# tt-motor_driver_and_encoder.net
KiCad netlist of a schematic drawn in EAGLE
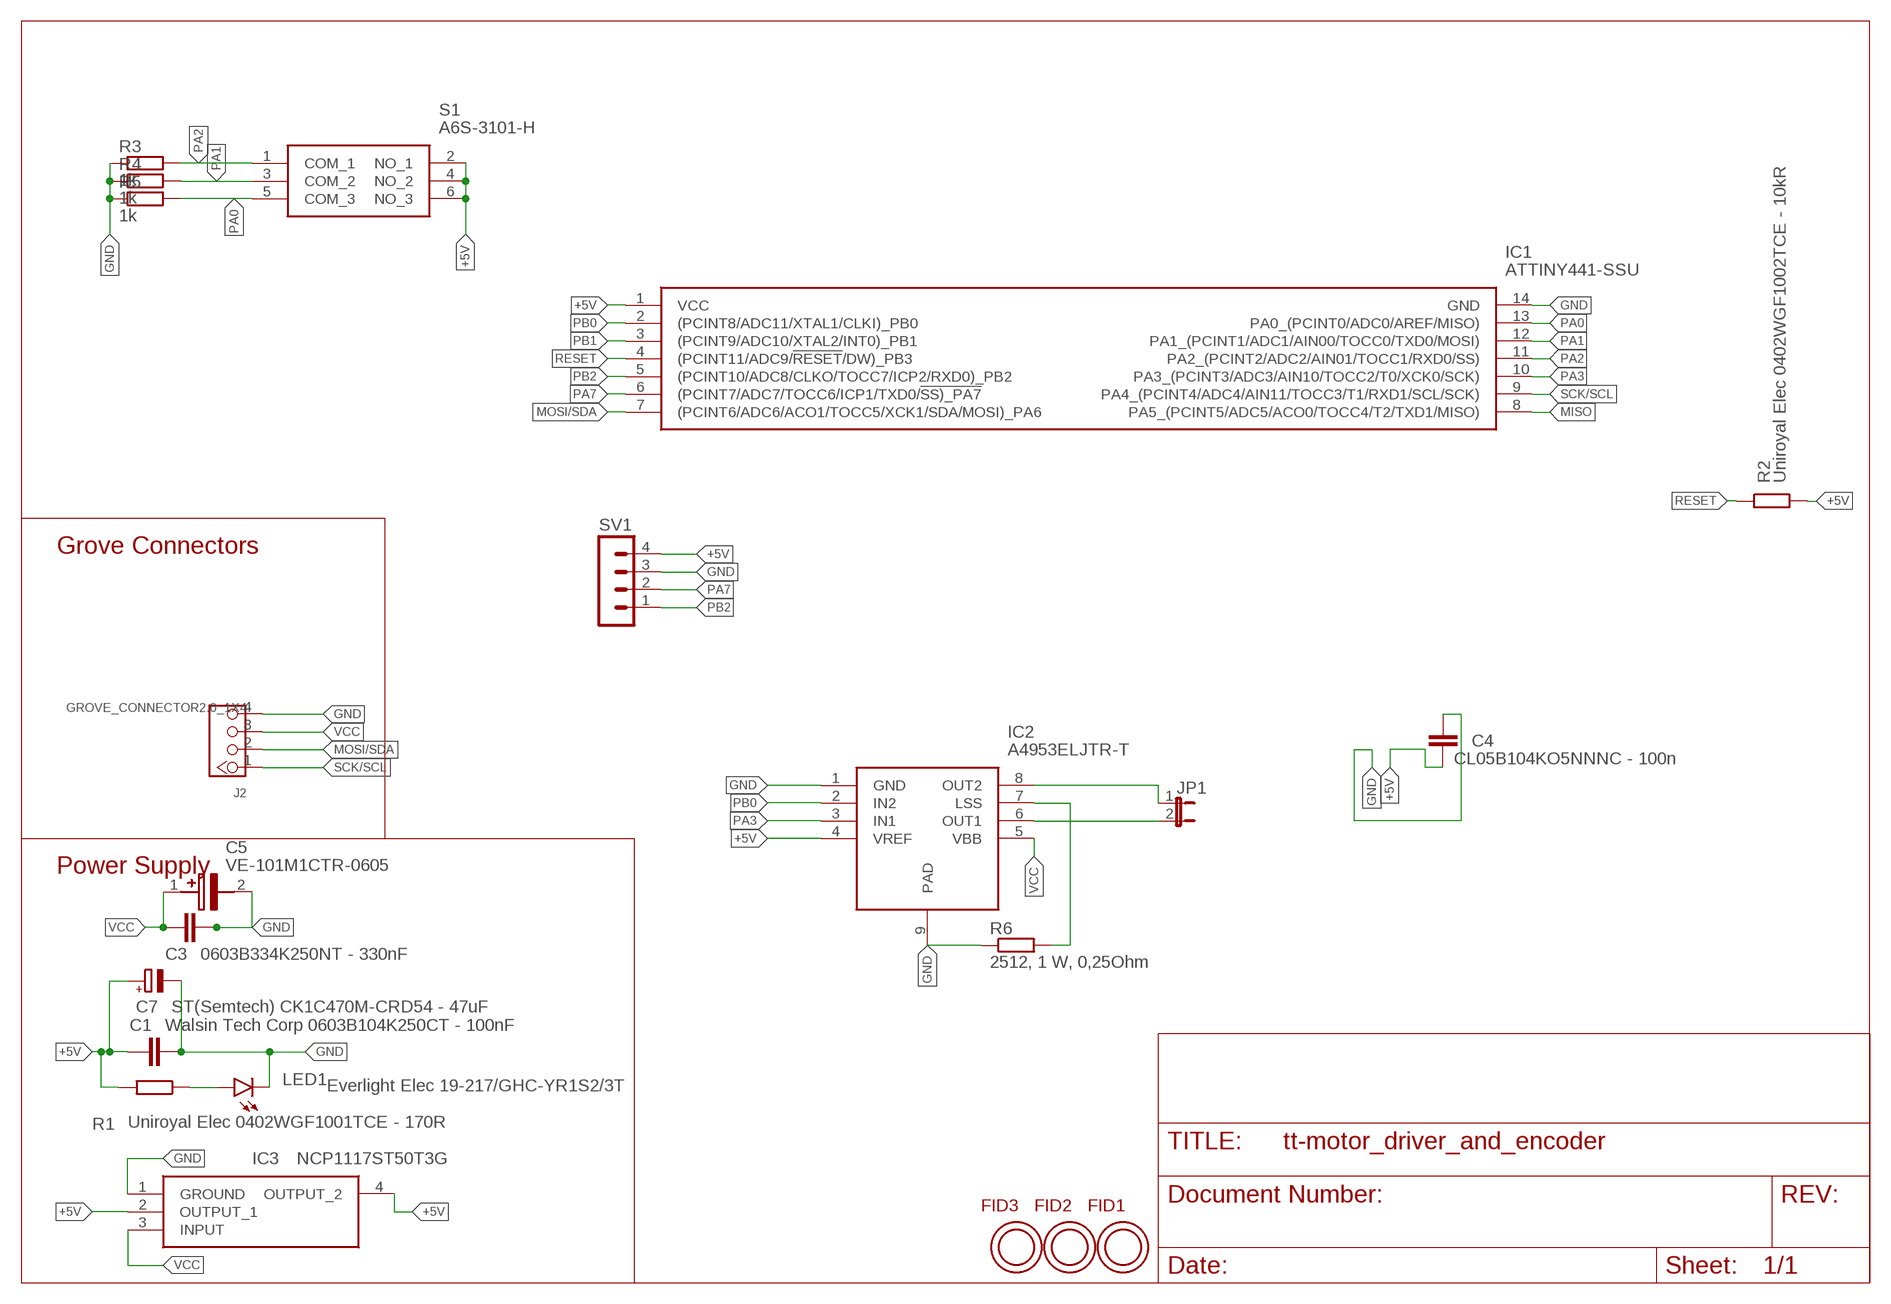
[diagram p0: schematic, sheet 1]

(export (version "E")
  (design (tool "Eeschema 10.0.6"))
  (components
    (comp (ref "C1")
      (value "Walsin Tech Corp 0603B104K250CT - 100nF")
      (footprint "eagle-import:C0603")
      (libsource (lib "eagle-import") (part "C-EUC0603"))
    )
    (comp (ref "C3")
      (value "0603B334K250NT - 330nF")
      (footprint "eagle-import:C0603")
      (libsource (lib "eagle-import") (part "C-EUC0603"))
    )
    (comp (ref "C4")
      (value "CL05B104KO5NNNC - 100n")
      (footprint "eagle-import:C0402")
      (libsource (lib "eagle-import") (part "C-EUC0402"))
    )
    (comp (ref "C5")
      (value "VE-101M1CTR-0605")
      (footprint "eagle-import:CAPAE660X550N")
      (fields (field (name "MOUSER_PART_NUMBER") "140-VE101M1CTR0605"))
      (libsource (lib "eagle-import") (part "VE-101M1CTR-0605"))
    )
    (comp (ref "C7")
      (value "ST(Semtech) CK1C470M-CRD54 - 47uF")
      (footprint "eagle-import:PANASONIC_C")
      (libsource (lib "eagle-import") (part "CPOL-EUC"))
    )
    (comp (ref "FID1")
      (value "OPEN-PNP-FIDUCIAL")
      (footprint "eagle-import:OPEN-PNP-FIDUCIAL")
      (libsource (lib "eagle-import") (part "OPEN-PNP-FIDUCIAL"))
    )
    (comp (ref "FID2")
      (value "OPEN-PNP-FIDUCIAL")
      (footprint "eagle-import:OPEN-PNP-FIDUCIAL")
      (libsource (lib "eagle-import") (part "OPEN-PNP-FIDUCIAL"))
    )
    (comp (ref "FID3")
      (value "OPEN-PNP-FIDUCIAL")
      (footprint "eagle-import:OPEN-PNP-FIDUCIAL")
      (libsource (lib "eagle-import") (part "OPEN-PNP-FIDUCIAL"))
    )
    (comp (ref "IC1")
      (value "ATTINY441-SSU")
      (footprint "eagle-import:SOIC127P600X175-14N")
      (fields (field (name "MOUSER_PART_NUMBER") "556-ATTINY441-SSU"))
      (libsource (lib "eagle-import") (part "ATTINY441-SSU"))
    )
    (comp (ref "IC2")
      (value "A4953ELJTR-T")
      (footprint "eagle-import:SOIC127P600X170-9N")
      (libsource (lib "eagle-import") (part "A4953ELJTR-T"))
    )
    (comp (ref "IC3")
      (value "NCP1117ST50T3G")
      (footprint "eagle-import:SOT230P700X180-4N")
      (fields (field (name "MOUSER_PART_NUMBER") "863-NCP1117ST50T3G"))
      (libsource (lib "eagle-import") (part "NCP1117ST50T3G"))
    )
    (comp (ref "J2")
      (value "GROVE_CONNECTOR2.0_1X4")
      (footprint "eagle-import:2.0_1X4_STRAIGHT")
      (libsource (lib "eagle-import") (part "GROVE_CONNECTOR2.0_1X4"))
    )
    (comp (ref "JP1")
      (value "JP1E")
      (footprint "eagle-import:JP1")
      (libsource (lib "eagle-import") (part "JP1E"))
    )
    (comp (ref "LED1")
      (value "Everlight Elec 19-217/GHC-YR1S2/3T")
      (footprint "eagle-import:CHIPLED_0603")
      (libsource (lib "eagle-import") (part "LEDCHIPLED_0603"))
    )
    (comp (ref "R1")
      (value "Uniroyal Elec 0402WGF1001TCE - 170R")
      (footprint "eagle-import:R0402")
      (libsource (lib "eagle-import") (part "R-EU_R0402"))
    )
    (comp (ref "R2")
      (value "Uniroyal Elec 0402WGF1002TCE - 10kR")
      (footprint "eagle-import:R0402")
      (libsource (lib "eagle-import") (part "R-EU_R0402"))
    )
    (comp (ref "R3")
      (value "1k")
      (footprint "eagle-import:R0402")
      (libsource (lib "eagle-import") (part "R-EU_R0402"))
    )
    (comp (ref "R4")
      (value "1k")
      (footprint "eagle-import:R0402")
      (libsource (lib "eagle-import") (part "R-EU_R0402"))
    )
    (comp (ref "R5")
      (value "1k")
      (footprint "eagle-import:R0402")
      (libsource (lib "eagle-import") (part "R-EU_R0402"))
    )
    (comp (ref "R6")
      (value "2512, 1 W, 0,25Ohm")
      (footprint "eagle-import:R2512")
      (libsource (lib "eagle-import") (part "R-EU_R2512"))
    )
    (comp (ref "S1")
      (value "A6S-3101-H")
      (footprint "eagle-import:A6S3104H")
      (fields (field (name "MOUSER_PART_NUMBER") "653-A6S-3101-H"))
      (libsource (lib "eagle-import") (part "A6S-3101-H"))
    )
    (comp (ref "SV1")
      (value "MA04-1")
      (footprint "eagle-import:MA04-1")
      (libsource (lib "eagle-import") (part "MA04-1"))
    )
  )
  (nets
    (net (code "1") (name "+5V") (class "Default")
      (node (ref "C1") (pin "1") (pinfunction "1_1") (pintype "passive"))
      (node (ref "C4") (pin "1") (pinfunction "1_1") (pintype "passive"))
      (node (ref "C7") (pin "+") (pinfunction "+_+") (pintype "passive"))
      (node (ref "IC1") (pin "1") (pinfunction "VCC_1") (pintype "bidirectional"))
      (node (ref "IC2") (pin "4") (pinfunction "VREF_4") (pintype "input"))
      (node (ref "IC3") (pin "2") (pinfunction "OUTPUT_1_2") (pintype "bidirectional"))
      (node (ref "IC3") (pin "4") (pinfunction "OUTPUT_2_4") (pintype "bidirectional"))
      (node (ref "R1") (pin "2") (pinfunction "2_2") (pintype "passive"))
      (node (ref "R2") (pin "2") (pinfunction "2_2") (pintype "passive"))
      (node (ref "S1") (pin "2") (pinfunction "NO_1_2") (pintype "bidirectional"))
      (node (ref "S1") (pin "4") (pinfunction "NO_2_4") (pintype "bidirectional"))
      (node (ref "S1") (pin "6") (pinfunction "NO_3_6") (pintype "bidirectional"))
      (node (ref "SV1") (pin "4") (pinfunction "4_4") (pintype "passive"))
    )
    (net (code "2") (name "GND") (class "Default")
      (node (ref "C1") (pin "2") (pinfunction "2_2") (pintype "passive"))
      (node (ref "C3") (pin "1") (pinfunction "1_1") (pintype "passive"))
      (node (ref "C4") (pin "2") (pinfunction "2_2") (pintype "passive"))
      (node (ref "C5") (pin "2") (pinfunction "-_2") (pintype "bidirectional"))
      (node (ref "C7") (pin "-") (pinfunction "-_-") (pintype "passive"))
      (node (ref "IC1") (pin "14") (pinfunction "GND_14") (pintype "bidirectional"))
      (node (ref "IC2") (pin "1") (pinfunction "GND_1") (pintype "power_in"))
      (node (ref "IC2") (pin "9") (pinfunction "PAD_9") (pintype "bidirectional"))
      (node (ref "IC3") (pin "1") (pinfunction "GROUND_1") (pintype "bidirectional"))
      (node (ref "J2") (pin "4") (pinfunction "4_4") (pintype "bidirectional"))
      (node (ref "LED1") (pin "C") (pinfunction "C_C") (pintype "passive"))
      (node (ref "R3") (pin "1") (pinfunction "1_1") (pintype "passive"))
      (node (ref "R4") (pin "1") (pinfunction "1_1") (pintype "passive"))
      (node (ref "R5") (pin "1") (pinfunction "1_1") (pintype "passive"))
      (node (ref "R6") (pin "1") (pinfunction "1_1") (pintype "passive"))
      (node (ref "SV1") (pin "3") (pinfunction "3_3") (pintype "passive"))
    )
    (net (code "3") (name "MISO") (class "Default")
      (node (ref "IC1") (pin "8") (pinfunction "PA5_(PCINT5/ADC5/ACO0/TOCC4/T2/TXD1/MISO)_8") (pintype "bidirectional"))
    )
    (net (code "4") (name "MOSI{slash}SDA") (class "Default")
      (node (ref "IC1") (pin "7") (pinfunction "(PCINT6/ADC6/ACO1/TOCC5/XCK1/SDA/MOSI)_PA6_7") (pintype "bidirectional"))
      (node (ref "J2") (pin "2") (pinfunction "2_2") (pintype "bidirectional"))
    )
    (net (code "5") (name "Net-(IC2-LSS)") (class "Default")
      (node (ref "IC2") (pin "7") (pinfunction "LSS_7") (pintype "input"))
      (node (ref "R6") (pin "2") (pinfunction "2_2") (pintype "passive"))
    )
    (net (code "6") (name "Net-(IC2-OUT1)") (class "Default")
      (node (ref "IC2") (pin "6") (pinfunction "OUT1_6") (pintype "output"))
      (node (ref "JP1") (pin "2") (pinfunction "2_2") (pintype "passive"))
    )
    (net (code "7") (name "Net-(IC2-OUT2)") (class "Default")
      (node (ref "IC2") (pin "8") (pinfunction "OUT2_8") (pintype "output"))
      (node (ref "JP1") (pin "1") (pinfunction "1_1") (pintype "passive"))
    )
    (net (code "8") (name "Net-(LED1-PadA)") (class "Default")
      (node (ref "LED1") (pin "A") (pinfunction "A_A") (pintype "passive"))
      (node (ref "R1") (pin "1") (pinfunction "1_1") (pintype "passive"))
    )
    (net (code "9") (name "PA0") (class "Default")
      (node (ref "IC1") (pin "13") (pinfunction "PA0_(PCINT0/ADC0/AREF/MISO)_13") (pintype "bidirectional"))
      (node (ref "R5") (pin "2") (pinfunction "2_2") (pintype "passive"))
      (node (ref "S1") (pin "5") (pinfunction "COM_3_5") (pintype "bidirectional"))
    )
    (net (code "10") (name "PA1") (class "Default")
      (node (ref "IC1") (pin "12") (pinfunction "PA1_(PCINT1/ADC1/AIN00/TOCC0/TXD0/MOSI)_12") (pintype "bidirectional"))
      (node (ref "R4") (pin "2") (pinfunction "2_2") (pintype "passive"))
      (node (ref "S1") (pin "3") (pinfunction "COM_2_3") (pintype "bidirectional"))
    )
    (net (code "11") (name "PA2") (class "Default")
      (node (ref "IC1") (pin "11") (pinfunction "PA2_(PCINT2/ADC2/AIN01/TOCC1/RXD0/SS)_11") (pintype "bidirectional"))
      (node (ref "R3") (pin "2") (pinfunction "2_2") (pintype "passive"))
      (node (ref "S1") (pin "1") (pinfunction "COM_1_1") (pintype "bidirectional"))
    )
    (net (code "12") (name "PA3") (class "Default")
      (node (ref "IC1") (pin "10") (pinfunction "PA3_(PCINT3/ADC3/AIN10/TOCC2/T0/XCK0/SCK)_10") (pintype "bidirectional"))
      (node (ref "IC2") (pin "3") (pinfunction "IN1_3") (pintype "input"))
    )
    (net (code "13") (name "PA7") (class "Default")
      (node (ref "IC1") (pin "6") (pinfunction "(PCINT7/ADC7/TOCC6/ICP1/TXD0/~{SS})_PA7_6") (pintype "bidirectional"))
      (node (ref "SV1") (pin "2") (pinfunction "2_2") (pintype "passive"))
    )
    (net (code "14") (name "PB0") (class "Default")
      (node (ref "IC1") (pin "2") (pinfunction "(PCINT8/ADC11/XTAL1/CLKI)_PB0_2") (pintype "bidirectional"))
      (node (ref "IC2") (pin "2") (pinfunction "IN2_2") (pintype "input"))
    )
    (net (code "15") (name "PB1") (class "Default")
      (node (ref "IC1") (pin "3") (pinfunction "(PCINT9/ADC10/XTAL2/INT0)_PB1_3") (pintype "bidirectional"))
    )
    (net (code "16") (name "PB2") (class "Default")
      (node (ref "IC1") (pin "5") (pinfunction "(PCINT10/ADC8/CLKO/TOCC7/ICP2/RXD0)_PB2_5") (pintype "bidirectional"))
      (node (ref "SV1") (pin "1") (pinfunction "1_1") (pintype "passive"))
    )
    (net (code "17") (name "RESET") (class "Default")
      (node (ref "IC1") (pin "4") (pinfunction "(PCINT11/ADC9/~{RESET}/DW)_PB3_4") (pintype "bidirectional"))
      (node (ref "R2") (pin "1") (pinfunction "1_1") (pintype "passive"))
    )
    (net (code "18") (name "SCK{slash}SCL") (class "Default")
      (node (ref "IC1") (pin "9") (pinfunction "PA4_(PCINT4/ADC4/AIN11/TOCC3/T1/RXD1/SCL/SCK)_9") (pintype "bidirectional"))
      (node (ref "J2") (pin "1") (pinfunction "1_1") (pintype "bidirectional"))
    )
    (net (code "19") (name "VCC") (class "Default")
      (node (ref "C3") (pin "2") (pinfunction "2_2") (pintype "passive"))
      (node (ref "C5") (pin "1") (pinfunction "+_1") (pintype "bidirectional"))
      (node (ref "IC2") (pin "5") (pinfunction "VBB_5") (pintype "power_in"))
      (node (ref "IC3") (pin "3") (pinfunction "INPUT_3") (pintype "bidirectional"))
      (node (ref "J2") (pin "3") (pinfunction "3_3") (pintype "bidirectional"))
    )
  )
)
